# pc3_ext_lis3dh.net
KiCad netlist of a schematic drawn in EAGLE
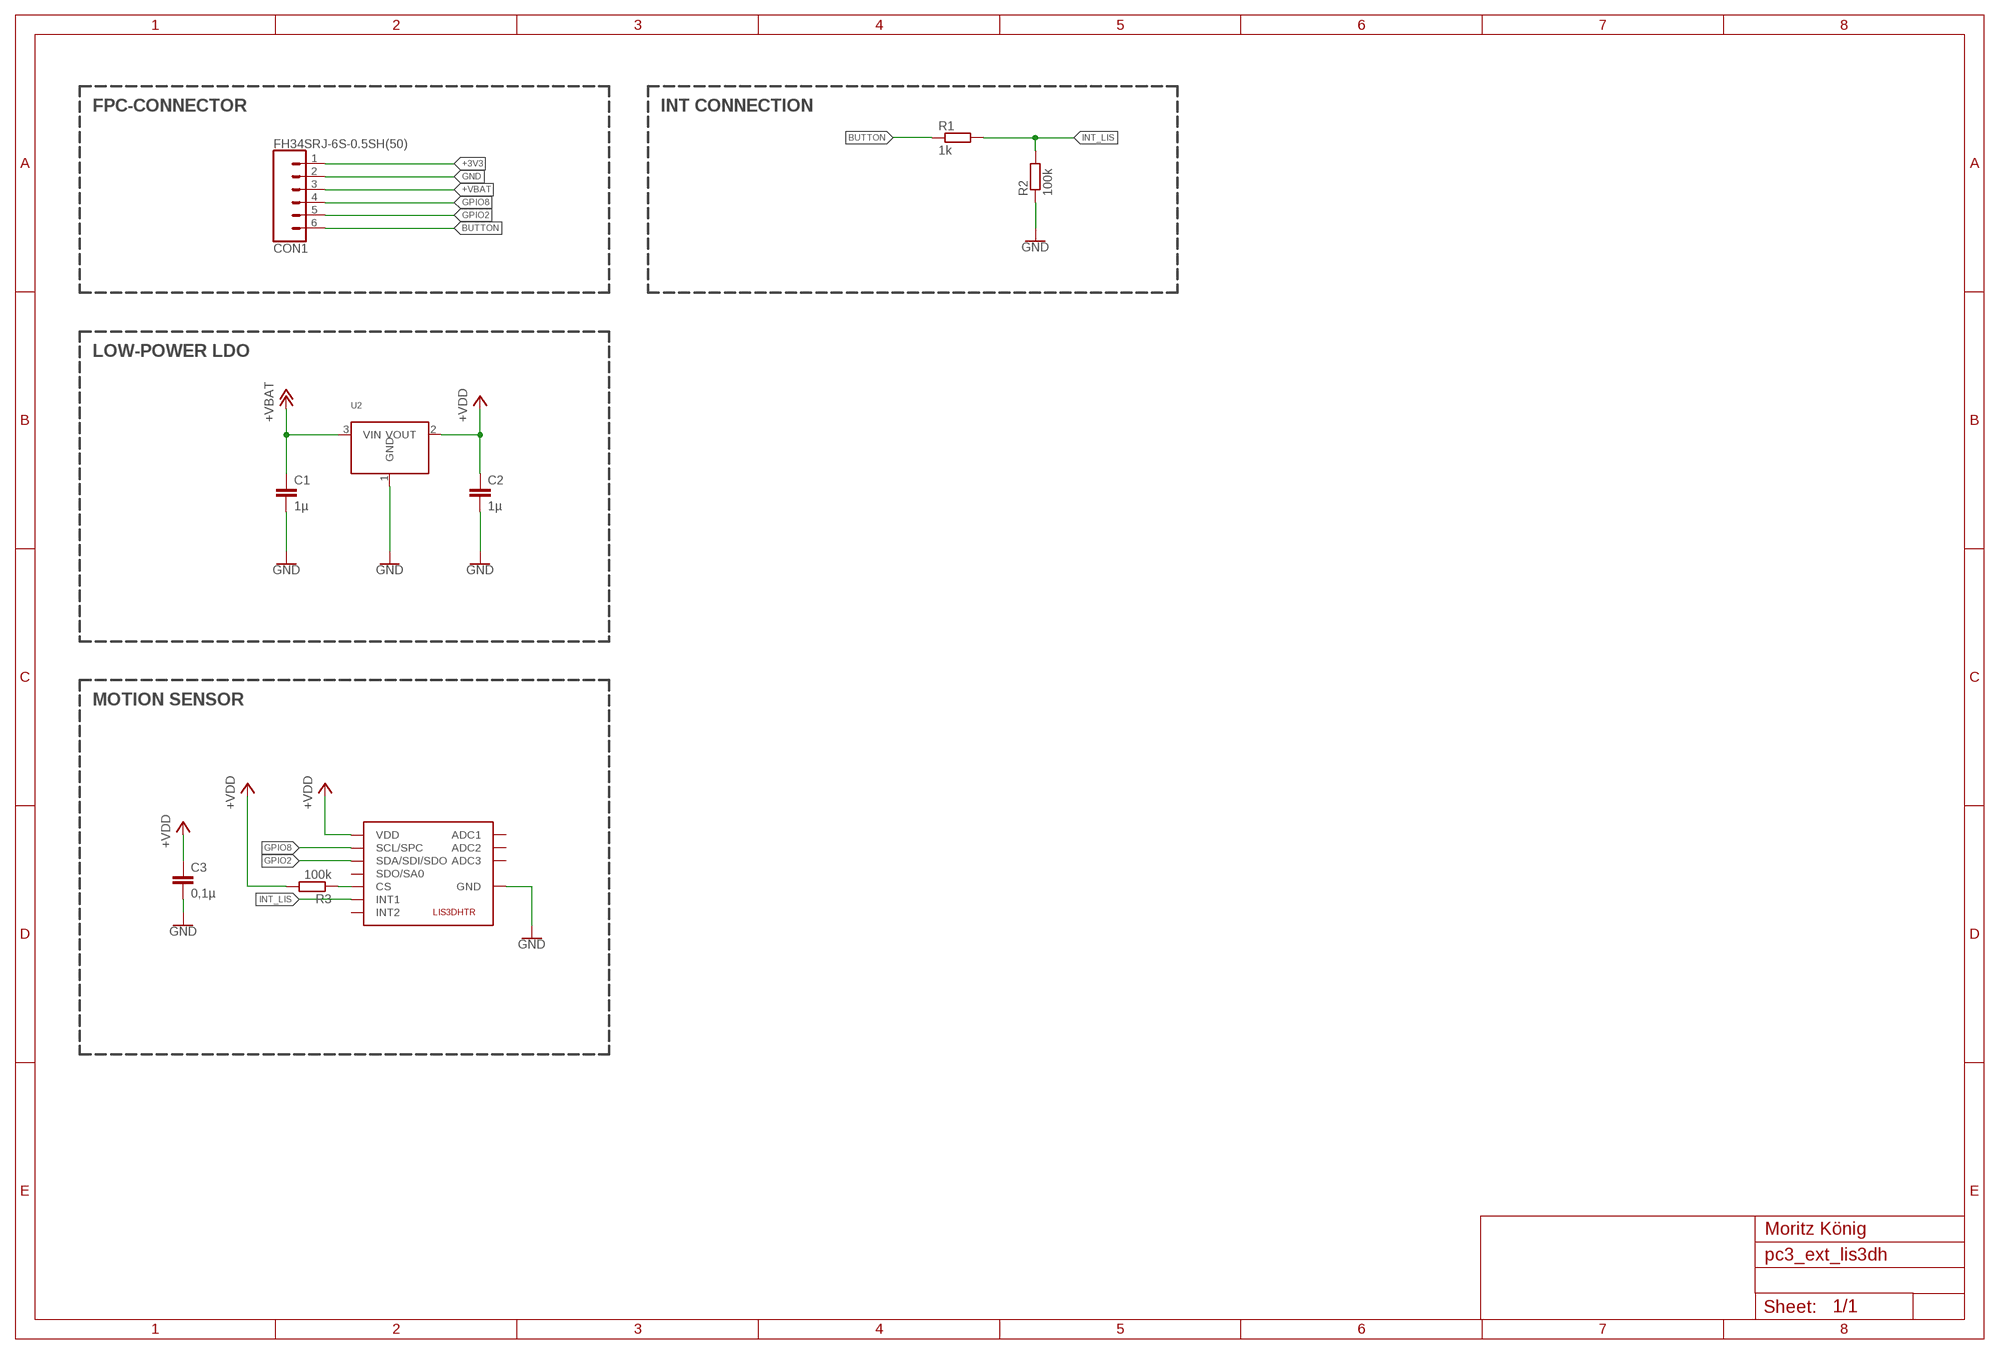
[diagram p0: schematic, sheet 1]

(export (version "E")
  (design (tool "Eeschema 10.0.6"))
  (components
    (comp (ref "C1")
      (value "1µ")
      (footprint "eagle-import:C0402_S")
      (libsource (lib "eagle-import") (part "C0402_S"))
    )
    (comp (ref "C2")
      (value "1µ")
      (footprint "eagle-import:C0402_S")
      (libsource (lib "eagle-import") (part "C0402_S"))
    )
    (comp (ref "C3")
      (value "0,1µ")
      (footprint "eagle-import:C0402_S")
      (libsource (lib "eagle-import") (part "C0402_S"))
    )
    (comp (ref "CON1")
      (value "FH34SRJ-6S-0.5SH(50)")
      (footprint "eagle-import:FH34SRJ-6S-0.5SH(50)")
      (libsource (lib "eagle-import") (part "FH34SRJ-6S-0.5SH(50)"))
    )
    (comp (ref "R1")
      (value "1k")
      (footprint "eagle-import:R0402")
      (libsource (lib "eagle-import") (part "R0402"))
    )
    (comp (ref "R2")
      (value "100k")
      (footprint "eagle-import:R0402")
      (libsource (lib "eagle-import") (part "R0402"))
    )
    (comp (ref "R3")
      (value "100k")
      (footprint "eagle-import:R0402")
      (libsource (lib "eagle-import") (part "R0402"))
    )
    (comp (ref "U1")
      (value "LIS3DHTR")
      (footprint "eagle-import:LGA_16_LIS3DHTR")
      (libsource (lib "eagle-import") (part "LIS3DHTR"))
    )
    (comp (ref "U2")
      (value "SE82XX")
      (footprint "eagle-import:SOT23-3")
      (libsource (lib "eagle-import") (part "SE82XX"))
    )
  )
  (nets
    (net (code "1") (name "+3V3") (class "Default")
      (node (ref "CON1") (pin "1") (pinfunction "1_1") (pintype "passive"))
    )
    (net (code "2") (name "+VBAT") (class "Default")
      (node (ref "C1") (pin "P$1") (pinfunction "1_P$1") (pintype "passive"))
      (node (ref "CON1") (pin "3") (pinfunction "3_3") (pintype "passive"))
      (node (ref "U2") (pin "3") (pinfunction "VIN_3") (pintype "bidirectional"))
    )
    (net (code "3") (name "+VDD") (class "Default")
      (node (ref "C2") (pin "P$1") (pinfunction "1_P$1") (pintype "passive"))
      (node (ref "C3") (pin "P$1") (pinfunction "1_P$1") (pintype "passive"))
      (node (ref "R3") (pin "2") (pinfunction "2_2") (pintype "passive"))
      (node (ref "U1") (pin "P$1") (pinfunction "VDD_P$1") (pintype "bidirectional"))
      (node (ref "U1") (pin "P$14") (pinfunction "VDD_P$14") (pintype "bidirectional"))
      (node (ref "U2") (pin "2") (pinfunction "VOUT_2") (pintype "bidirectional"))
    )
    (net (code "4") (name "BUTTON") (class "Default")
      (node (ref "CON1") (pin "6") (pinfunction "6_6") (pintype "passive"))
      (node (ref "R1") (pin "1") (pinfunction "1_1") (pintype "passive"))
    )
    (net (code "5") (name "GND") (class "Default")
      (node (ref "C1") (pin "P$2") (pinfunction "2_P$2") (pintype "passive"))
      (node (ref "C2") (pin "P$2") (pinfunction "2_P$2") (pintype "passive"))
      (node (ref "C3") (pin "P$2") (pinfunction "2_P$2") (pintype "passive"))
      (node (ref "CON1") (pin "2") (pinfunction "2_2") (pintype "passive"))
      (node (ref "R2") (pin "1") (pinfunction "1_1") (pintype "passive"))
      (node (ref "U1") (pin "P$10") (pinfunction "GND_P$10") (pintype "bidirectional"))
      (node (ref "U1") (pin "P$12") (pinfunction "GND_P$12") (pintype "bidirectional"))
      (node (ref "U1") (pin "P$5") (pinfunction "GND_P$5") (pintype "bidirectional"))
      (node (ref "U2") (pin "1") (pinfunction "GND_1") (pintype "bidirectional"))
    )
    (net (code "6") (name "GPIO2") (class "Default")
      (node (ref "CON1") (pin "5") (pinfunction "5_5") (pintype "passive"))
      (node (ref "U1") (pin "P$6") (pinfunction "SDA/SDI/SDO_P$6") (pintype "bidirectional"))
    )
    (net (code "7") (name "GPIO8") (class "Default")
      (node (ref "CON1") (pin "4") (pinfunction "4_4") (pintype "passive"))
      (node (ref "U1") (pin "P$4") (pinfunction "SCL/SPC_P$4") (pintype "bidirectional"))
    )
    (net (code "8") (name "INT_LIS") (class "Default")
      (node (ref "R1") (pin "2") (pinfunction "2_2") (pintype "passive"))
      (node (ref "R2") (pin "2") (pinfunction "2_2") (pintype "passive"))
      (node (ref "U1") (pin "P$11") (pinfunction "INT1_P$11") (pintype "bidirectional"))
    )
    (net (code "9") (name "Net-(U1-CS)") (class "Default")
      (node (ref "R3") (pin "1") (pinfunction "1_1") (pintype "passive"))
      (node (ref "U1") (pin "P$8") (pinfunction "CS_P$8") (pintype "bidirectional"))
    )
    (net (code "10") (name "unconnected-(U1-ADC1-PadP$16)") (class "Default")
      (node (ref "U1") (pin "P$16") (pinfunction "ADC1_P$16") (pintype "bidirectional"))
    )
    (net (code "11") (name "unconnected-(U1-ADC2-PadP$15)") (class "Default")
      (node (ref "U1") (pin "P$15") (pinfunction "ADC2_P$15") (pintype "bidirectional"))
    )
    (net (code "12") (name "unconnected-(U1-ADC3-PadP$13)") (class "Default")
      (node (ref "U1") (pin "P$13") (pinfunction "ADC3_P$13") (pintype "bidirectional"))
    )
    (net (code "13") (name "unconnected-(U1-INT2-PadP$9)") (class "Default")
      (node (ref "U1") (pin "P$9") (pinfunction "INT2_P$9") (pintype "bidirectional"))
    )
    (net (code "14") (name "unconnected-(U1-SDO{slash}SA0-PadP$7)") (class "Default")
      (node (ref "U1") (pin "P$7") (pinfunction "SDO/SA0_P$7") (pintype "bidirectional"))
    )
  )
)
